# Color2018.net
KiCad netlist of a schematic drawn in EAGLE
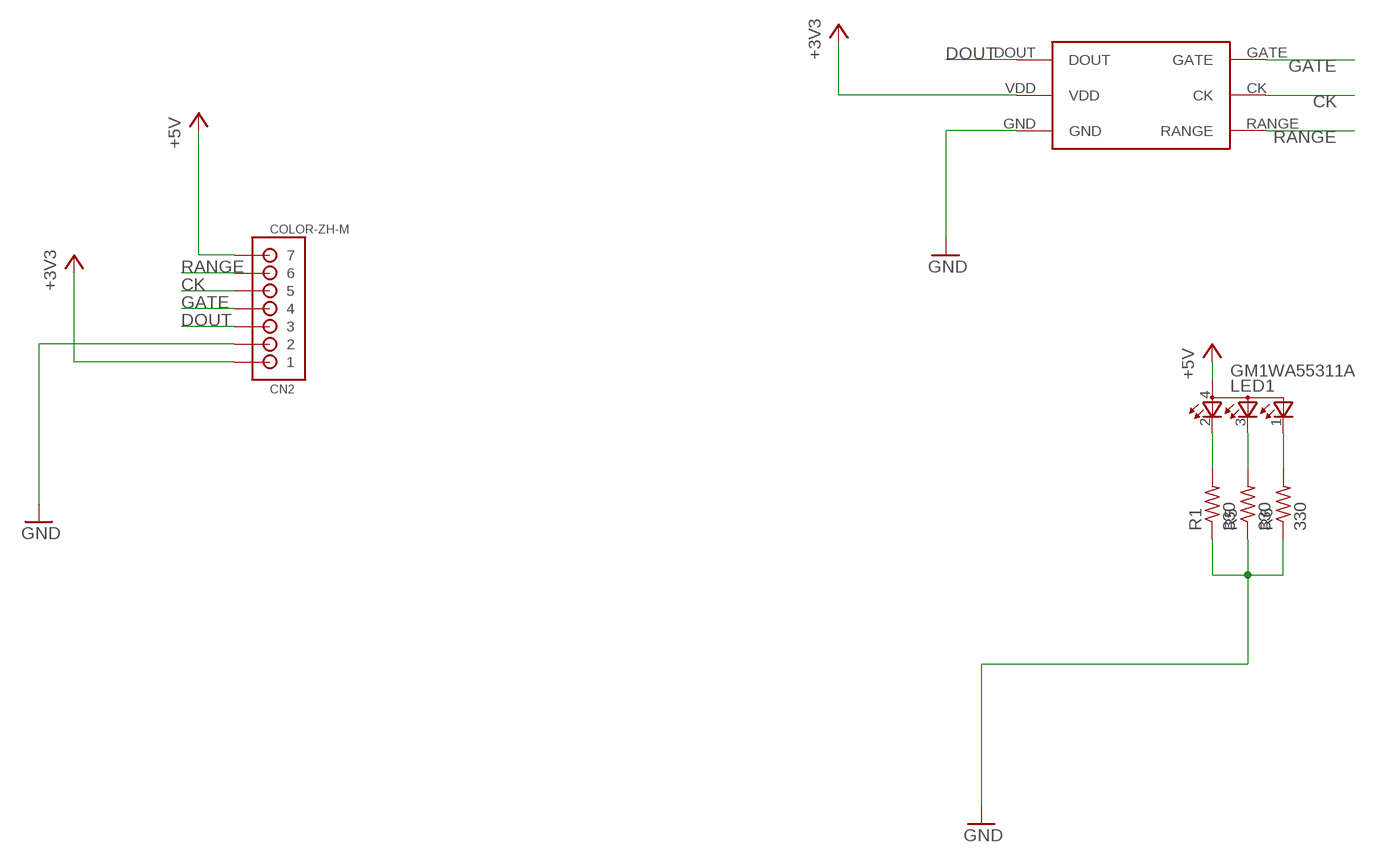
[diagram p0: schematic, sheet 1]

(export (version "E")
  (design (tool "Eeschema 10.0.6"))
  (components
    (comp (ref "CN2")
      (value "COLOR-ZH-M")
      (footprint "eagle-import:B7B-ZR")
      (libsource (lib "eagle-import") (part "B7B-ZR"))
    )
    (comp (ref "LED1")
      (value "GM1WA55311A")
      (footprint "eagle-import:GM1WA55311A")
      (libsource (lib "eagle-import") (part "GM1WA55311A"))
    )
    (comp (ref "R1")
      (value "330")
      (footprint "eagle-import:R0805")
      (libsource (lib "eagle-import") (part "R-US_R0805"))
    )
    (comp (ref "R5")
      (value "330")
      (footprint "eagle-import:R0805")
      (libsource (lib "eagle-import") (part "R-US_R0805"))
    )
    (comp (ref "R6")
      (value "330")
      (footprint "eagle-import:R0805")
      (libsource (lib "eagle-import") (part "R-US_R0805"))
    )
    (comp (ref "U$1")
      (value "S9706")
      (footprint "eagle-import:S9706")
      (libsource (lib "eagle-import") (part "S9706"))
    )
  )
  (nets
    (net (code "1") (name "+3V3") (class "Default")
      (node (ref "CN2") (pin "1") (pinfunction "1_1") (pintype "bidirectional"))
      (node (ref "U$1") (pin "VDD") (pinfunction "VDD_VDD") (pintype "bidirectional"))
    )
    (net (code "2") (name "+5V") (class "Default")
      (node (ref "CN2") (pin "7") (pinfunction "7_7") (pintype "bidirectional"))
      (node (ref "LED1") (pin "4") (pinfunction "A_4") (pintype "passive"))
    )
    (net (code "3") (name "/CK") (class "Default")
      (node (ref "CN2") (pin "5") (pinfunction "5_5") (pintype "bidirectional"))
      (node (ref "U$1") (pin "CK") (pinfunction "CK_CK") (pintype "bidirectional"))
    )
    (net (code "4") (name "/DOUT") (class "Default")
      (node (ref "CN2") (pin "3") (pinfunction "3_3") (pintype "bidirectional"))
      (node (ref "U$1") (pin "DOUT") (pinfunction "DOUT_DOUT") (pintype "bidirectional"))
    )
    (net (code "5") (name "/GATE") (class "Default")
      (node (ref "CN2") (pin "4") (pinfunction "4_4") (pintype "bidirectional"))
      (node (ref "U$1") (pin "GATE") (pinfunction "GATE_GATE") (pintype "bidirectional"))
    )
    (net (code "6") (name "/RANGE") (class "Default")
      (node (ref "CN2") (pin "6") (pinfunction "6_6") (pintype "bidirectional"))
      (node (ref "U$1") (pin "RANGE") (pinfunction "RANGE_RANGE") (pintype "bidirectional"))
    )
    (net (code "7") (name "GND") (class "Default")
      (node (ref "CN2") (pin "2") (pinfunction "2_2") (pintype "bidirectional"))
      (node (ref "R1") (pin "1") (pinfunction "1_1") (pintype "passive"))
      (node (ref "R5") (pin "1") (pinfunction "1_1") (pintype "passive"))
      (node (ref "R6") (pin "1") (pinfunction "1_1") (pintype "passive"))
      (node (ref "U$1") (pin "GND") (pinfunction "GND_GND") (pintype "bidirectional"))
    )
    (net (code "8") (name "Net-(LED1-CBLUE)") (class "Default")
      (node (ref "LED1") (pin "3") (pinfunction "CBLUE_3") (pintype "passive"))
      (node (ref "R5") (pin "2") (pinfunction "2_2") (pintype "passive"))
    )
    (net (code "9") (name "Net-(LED1-CGREEN)") (class "Default")
      (node (ref "LED1") (pin "1") (pinfunction "CGREEN_1") (pintype "passive"))
      (node (ref "R6") (pin "2") (pinfunction "2_2") (pintype "passive"))
    )
    (net (code "10") (name "Net-(LED1-CRED)") (class "Default")
      (node (ref "LED1") (pin "2") (pinfunction "CRED_2") (pintype "passive"))
      (node (ref "R1") (pin "2") (pinfunction "2_2") (pintype "passive"))
    )
  )
)
